# motherboard.net
KiCad netlist of a schematic drawn in Altium Designer
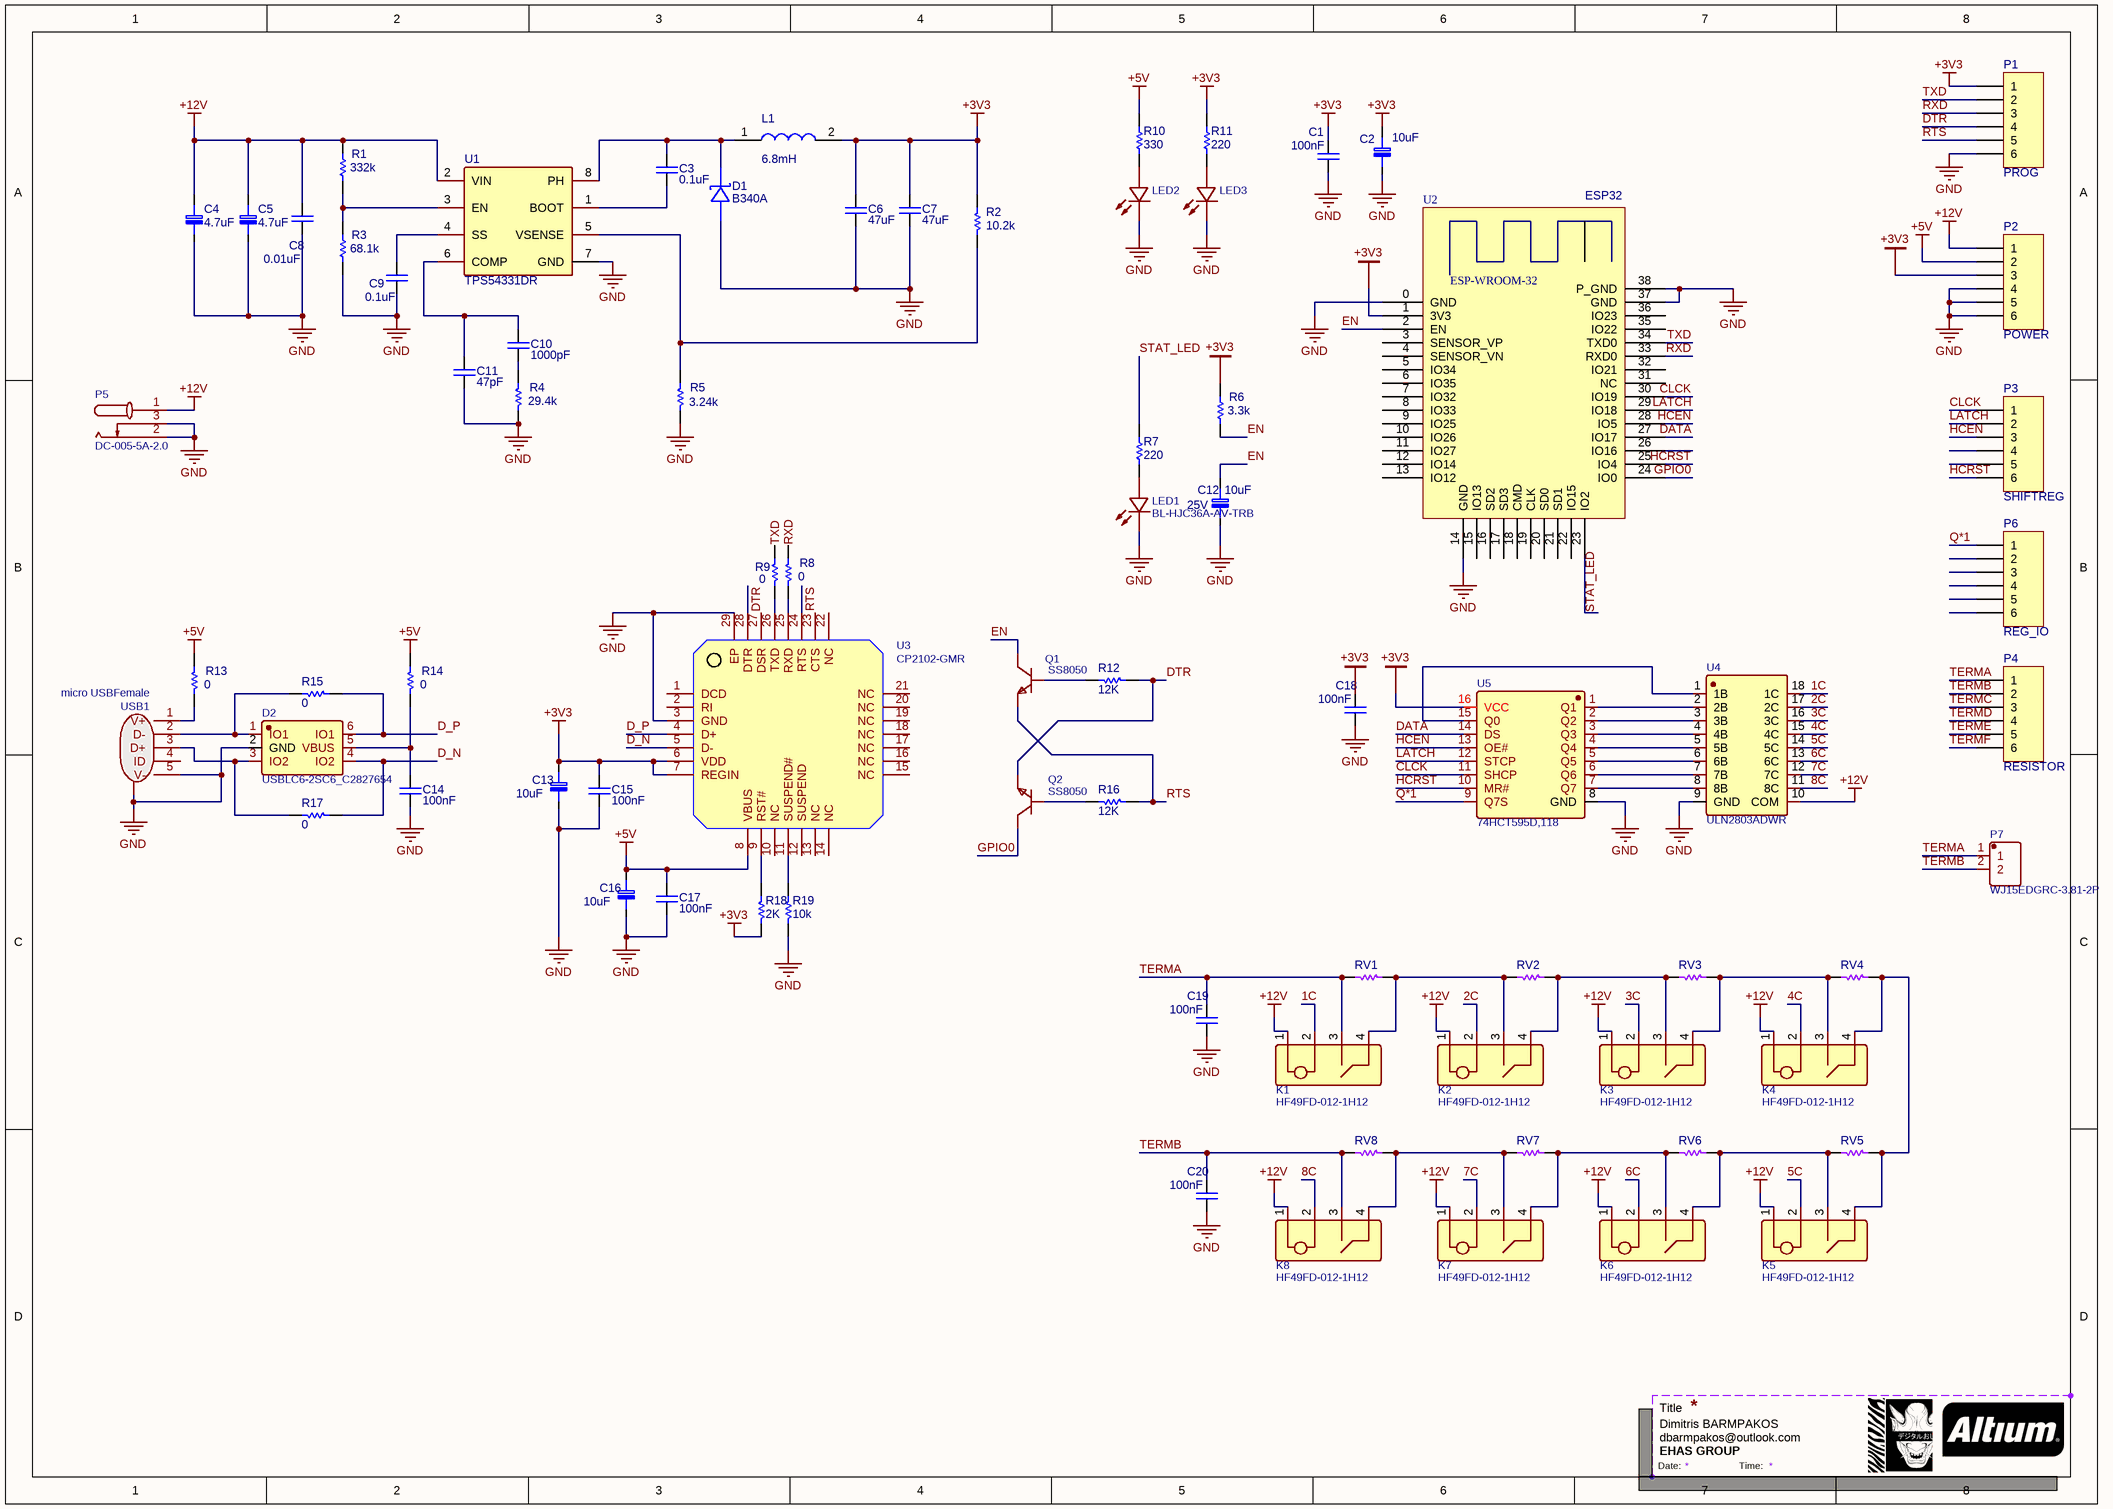
[diagram p0: motherboard.SchDoc]

(export (version "E")
  (design (tool "Eeschema 10.0.6"))
  (components
    (comp (ref "C1")
      (value "100nF")
      (footprint "CAP_0603")
      (description "CAP CER 0.1UF 50V X7R 0603")
      (fields
        (field (name "MANUFACTURER") "FH(Guangdong Fenghua Advanced Tech)")
        (field (name "MANUFACTURER PART NUMBER") "0603F104M500NT")
      )
      (libsource (lib "Schlib1") (part "CAP - CER 0.1UF 25V X7R 0805"))
    )
    (comp (ref "C2")
      (value "22uF 63V")
      (footprint "CAP SMD 6.3X7.7")
      (description "CAP ALUM 22UF 20% 25V SMD")
      (fields
        (field (name "MANUFACTURER") "Nichicon")
        (field (name "MANUFACTURER PART NUMBER") "UWX1E220MCL1GB")
        (field (name "CAPACITANCE") "10uF")
      )
      (libsource (lib "decade_box_lib") (part "CAP POL SMD"))
    )
    (comp (ref "C3")
      (value "0.1uF")
      (footprint "CAP_0603_3D")
      (description "CAP CER 0.1uF 50V C0G/NPO 0603")
      (fields
        (field (name "MANUFACTURER") "Yageo")
        (field (name "MANUFACTURER PART NUMBER") "CC0603JRNPO9BN220")
      )
      (libsource (lib "CC_Main_Lower") (part "Cap 22pF"))
    )
    (comp (ref "C4")
      (value "4.7uF")
      (footprint "CAP-SMD_BD6.3-L6.6-W6.6-LS7.2-R-RD")
      (description "CAP ALUM 22UF 20% 25V SMD")
      (fields
        (field (name "MANUFACTURER") "Nichicon")
        (field (name "MANUFACTURER PART NUMBER") "UWX1E220MCL1GB")
        (field (name "CAPACITANCE") "4.7uF")
      )
      (libsource (lib "decade_box_lib") (part "CAP POL SMD"))
    )
    (comp (ref "C5")
      (value "22uF 63V")
      (footprint "CAP-SMD_BD6.3-L6.6-W6.6-LS7.2-R-RD")
      (description "CAP ALUM 22UF 20% 25V SMD")
      (fields
        (field (name "MANUFACTURER") "Nichicon")
        (field (name "MANUFACTURER PART NUMBER") "UWX1E220MCL1GB")
        (field (name "CAPACITANCE") "4.7uF")
      )
      (libsource (lib "decade_box_lib") (part "CAP POL SMD"))
    )
    (comp (ref "C6")
      (value "47uF")
      (footprint "CAP_0603_3D")
      (description "CAP CER 0.1uF 50V C0G/NPO 0603")
      (fields
        (field (name "MANUFACTURER") "Yageo")
        (field (name "MANUFACTURER PART NUMBER") "CC0603JRNPO9BN220")
      )
      (libsource (lib "CC_Main_Lower") (part "Cap 22pF"))
    )
    (comp (ref "C7")
      (value "47uF")
      (footprint "CAP_0603_3D")
      (description "CAP CER 0.1uF 50V C0G/NPO 0603")
      (fields
        (field (name "MANUFACTURER") "Yageo")
        (field (name "MANUFACTURER PART NUMBER") "CC0603JRNPO9BN220")
      )
      (libsource (lib "CC_Main_Lower") (part "Cap 22pF"))
    )
    (comp (ref "C8")
      (value "0.01uF")
      (footprint "CAP_0603_3D")
      (description "CAP CER 0.1uF 50V C0G/NPO 0603")
      (fields
        (field (name "MANUFACTURER") "Yageo")
        (field (name "MANUFACTURER PART NUMBER") "CC0603JRNPO9BN220")
      )
      (libsource (lib "CC_Main_Lower") (part "Cap 22pF"))
    )
    (comp (ref "C9")
      (value "0.1uF")
      (footprint "CAP_0603_3D")
      (description "CAP CER 0.1uF 50V C0G/NPO 0603")
      (fields
        (field (name "MANUFACTURER") "Yageo")
        (field (name "MANUFACTURER PART NUMBER") "CC0603JRNPO9BN220")
      )
      (libsource (lib "CC_Main_Lower") (part "Cap 22pF"))
    )
    (comp (ref "C10")
      (value "1000pF")
      (footprint "CAP_0603_3D")
      (description "CAP CER 0.1uF 50V C0G/NPO 0603")
      (fields
        (field (name "MANUFACTURER") "Yageo")
        (field (name "MANUFACTURER PART NUMBER") "CC0603JRNPO9BN220")
      )
      (libsource (lib "CC_Main_Lower") (part "Cap 22pF"))
    )
    (comp (ref "C11")
      (value "47pF")
      (footprint "CAP_0603_3D")
      (description "CAP CER 0.1uF 50V C0G/NPO 0603")
      (fields
        (field (name "MANUFACTURER") "Yageo")
        (field (name "MANUFACTURER PART NUMBER") "CC0603JRNPO9BN220")
      )
      (libsource (lib "CC_Main_Lower") (part "Cap 22pF"))
    )
    (comp (ref "C12")
      (value "22uF 63V")
      (footprint "CAP SMD 6.3X7.7")
      (description "CAP ALUM 22UF 20% 25V SMD")
      (fields
        (field (name "MANUFACTURER") "Nichicon")
        (field (name "MANUFACTURER PART NUMBER") "UWX1E220MCL1GB")
        (field (name "CAPACITANCE") "10uF")
        (field (name "VOLTAGE RATING") "25V")
      )
      (libsource (lib "Schlib1") (part "CAP 22UF 63V SMD"))
    )
    (comp (ref "C13")
      (value "4.7uF")
      (footprint "CAP-SMD_BD6.3-L6.6-W6.6-LS7.2-R-RD")
      (description "CAP ALUM 22UF 20% 25V SMD")
      (fields
        (field (name "MANUFACTURER") "Nichicon")
        (field (name "MANUFACTURER PART NUMBER") "UWX1E220MCL1GB")
        (field (name "CAPACITANCE") "10uF")
      )
      (libsource (lib "decade_box_lib") (part "CAP POL SMD"))
    )
    (comp (ref "C14")
      (value "100nF")
      (footprint "CAP_0603_3D")
      (description "CAP CER 0.1uF 50V C0G/NPO 0603")
      (fields
        (field (name "MANUFACTURER") "Yageo")
        (field (name "MANUFACTURER PART NUMBER") "CC0603JRNPO9BN220")
      )
      (libsource (lib "CC_Main_Lower") (part "Cap 22pF"))
    )
    (comp (ref "C15")
      (value "100nF")
      (footprint "CAP_0603_3D")
      (description "CAP CER 0.1uF 50V C0G/NPO 0603")
      (fields
        (field (name "MANUFACTURER") "Yageo")
        (field (name "MANUFACTURER PART NUMBER") "CC0603JRNPO9BN220")
      )
      (libsource (lib "CC_Main_Lower") (part "Cap 22pF"))
    )
    (comp (ref "C16")
      (value "4.7uF")
      (footprint "CAP-SMD_BD6.3-L6.6-W6.6-LS7.2-R-RD")
      (description "CAP ALUM 22UF 20% 25V SMD")
      (fields
        (field (name "MANUFACTURER") "Nichicon")
        (field (name "MANUFACTURER PART NUMBER") "UWX1E220MCL1GB")
        (field (name "CAPACITANCE") "10uF")
      )
      (libsource (lib "decade_box_lib") (part "CAP POL SMD"))
    )
    (comp (ref "C17")
      (value "100nF")
      (footprint "CAP_0603_3D")
      (description "CAP CER 0.1uF 50V C0G/NPO 0603")
      (fields
        (field (name "MANUFACTURER") "Yageo")
        (field (name "MANUFACTURER PART NUMBER") "CC0603JRNPO9BN220")
      )
      (libsource (lib "CC_Main_Lower") (part "Cap 22pF"))
    )
    (comp (ref "C18")
      (value "100nF")
      (footprint "CAP_0603")
      (description "CAP CER 0.1UF 50V X7R 0603")
      (fields
        (field (name "MANUFACTURER") "FH(Guangdong Fenghua Advanced Tech)")
        (field (name "MANUFACTURER PART NUMBER") "0603F104M500NT")
      )
      (libsource (lib "Schlib1") (part "CAP - CER 0.1UF 25V X7R 0805"))
    )
    (comp (ref "C19")
      (value "100nF")
      (footprint "CAP_0603")
      (description "CAP CER 0.1UF 50V X7R 0603")
      (fields
        (field (name "MANUFACTURER") "FH(Guangdong Fenghua Advanced Tech)")
        (field (name "MANUFACTURER PART NUMBER") "0603F104M500NT")
      )
      (libsource (lib "Schlib1") (part "CAP - CER 0.1UF 25V X7R 0805"))
    )
    (comp (ref "C20")
      (value "100nF")
      (footprint "CAP_0603")
      (description "CAP CER 0.1UF 50V X7R 0603")
      (fields
        (field (name "MANUFACTURER") "FH(Guangdong Fenghua Advanced Tech)")
        (field (name "MANUFACTURER PART NUMBER") "0603F104M500NT")
      )
      (libsource (lib "Schlib1") (part "CAP - CER 0.1UF 25V X7R 0805"))
    )
    (comp (ref "D1")
      (value "B340A")
      (footprint "SMA_L4.3-W2.6-LS5.2-RD")
      (fields (field (name "BOM_SUPPLIER PART") "C64982"))
      (libsource (lib "decade_box_lib") (part "B340A"))
    )
    (comp (ref "D2")
      (value "USBLC6-2SC6_C2827654")
      (footprint "SOT-23-6_L2.9-W1.6-P0.95-LS2.8-BL")
      (fields
        (field (name "BOM_SUPPLIER PART") "C2827654")
        (field (name "BOM_MANUFACTURER PART") "USBLC6-2SC6")
        (field (name "CONTRIBUTOR") "LCSC")
      )
      (libsource (lib "decade_box_lib") (part "USBLC6-2SC6_C2827654"))
    )
    (comp (ref "K1")
      (value "HF49FD-012-1H12")
      (footprint "RELAY-TH_HF49FD-0XX-1H12")
      (fields (field (name "BOM_SUPPLIER PART") "C117488") (field (name "CONTRIBUTOR") "LCSC"))
      (libsource (lib "decade_box_lib") (part "HF49FD-012-1H12"))
    )
    (comp (ref "K2")
      (value "HF49FD-012-1H12")
      (footprint "RELAY-TH_HF49FD-0XX-1H12")
      (fields (field (name "BOM_SUPPLIER PART") "C117488") (field (name "CONTRIBUTOR") "LCSC"))
      (libsource (lib "decade_box_lib") (part "HF49FD-012-1H12"))
    )
    (comp (ref "K3")
      (value "HF49FD-012-1H12")
      (footprint "RELAY-TH_HF49FD-0XX-1H12")
      (fields (field (name "BOM_SUPPLIER PART") "C117488") (field (name "CONTRIBUTOR") "LCSC"))
      (libsource (lib "decade_box_lib") (part "HF49FD-012-1H12"))
    )
    (comp (ref "K4")
      (value "HF49FD-012-1H12")
      (footprint "RELAY-TH_HF49FD-0XX-1H12")
      (fields (field (name "BOM_SUPPLIER PART") "C117488") (field (name "CONTRIBUTOR") "LCSC"))
      (libsource (lib "decade_box_lib") (part "HF49FD-012-1H12"))
    )
    (comp (ref "K5")
      (value "HF49FD-012-1H12")
      (footprint "RELAY-TH_HF49FD-0XX-1H12")
      (fields (field (name "BOM_SUPPLIER PART") "C117488") (field (name "CONTRIBUTOR") "LCSC"))
      (libsource (lib "decade_box_lib") (part "HF49FD-012-1H12"))
    )
    (comp (ref "K6")
      (value "HF49FD-012-1H12")
      (footprint "RELAY-TH_HF49FD-0XX-1H12")
      (fields (field (name "BOM_SUPPLIER PART") "C117488") (field (name "CONTRIBUTOR") "LCSC"))
      (libsource (lib "decade_box_lib") (part "HF49FD-012-1H12"))
    )
    (comp (ref "K7")
      (value "HF49FD-012-1H12")
      (footprint "RELAY-TH_HF49FD-0XX-1H12")
      (fields (field (name "BOM_SUPPLIER PART") "C117488") (field (name "CONTRIBUTOR") "LCSC"))
      (libsource (lib "decade_box_lib") (part "HF49FD-012-1H12"))
    )
    (comp (ref "K8")
      (value "HF49FD-012-1H12")
      (footprint "RELAY-TH_HF49FD-0XX-1H12")
      (fields (field (name "BOM_SUPPLIER PART") "C117488") (field (name "CONTRIBUTOR") "LCSC"))
      (libsource (lib "decade_box_lib") (part "HF49FD-012-1H12"))
    )
    (comp (ref "L1")
      (value "6.8mH")
      (footprint "L_4018")
      (description "C393989")
      (libsource (lib "Schlib1") (part "L"))
    )
    (comp (ref "LED1")
      (value "BL-HJC36A-AV-TRB")
      (footprint "LED0603-RD_ORANGE")
      (fields (field (name "BOM_SUPPLIER PART") "C138546") (field (name "CONTRIBUTOR") "LCSC"))
      (libsource (lib "decade_box_lib") (part "BL-HJC36A-AV-TRB"))
    )
    (comp (ref "LED2")
      (value "BL-HJC36A-AV-TRB")
      (footprint "LED0603-RD_ORANGE")
      (fields (field (name "BOM_SUPPLIER PART") "C138546") (field (name "CONTRIBUTOR") "LCSC"))
      (libsource (lib "decade_box_lib") (part "BL-HJC36A-AV-TRB"))
    )
    (comp (ref "LED3")
      (value "BL-HJC36A-AV-TRB")
      (footprint "LED0603-RD_ORANGE")
      (fields (field (name "BOM_SUPPLIER PART") "C138546") (field (name "CONTRIBUTOR") "LCSC"))
      (libsource (lib "decade_box_lib") (part "BL-HJC36A-AV-TRB"))
    )
    (comp (ref "P1")
      (value "PROG")
      (footprint "HDR1X6")
      (description "Header, 6-Pin")
      (fields (field (name "PUBLISHER") "Altium Limited"))
      (libsource (lib "decade_box_lib") (part "Header 6"))
    )
    (comp (ref "P2")
      (value "POWER")
      (footprint "HDR1X6")
      (description "Header, 6-Pin")
      (fields (field (name "PUBLISHER") "Altium Limited"))
      (libsource (lib "decade_box_lib") (part "Header 6"))
    )
    (comp (ref "P3")
      (value "SHIFTREG")
      (footprint "HDR1X6")
      (description "Header, 6-Pin")
      (fields (field (name "PUBLISHER") "Altium Limited"))
      (libsource (lib "decade_box_lib") (part "Header 6"))
    )
    (comp (ref "P4")
      (value "RESISTOR")
      (footprint "HDR1X6")
      (description "Header, 6-Pin")
      (fields (field (name "PUBLISHER") "Altium Limited"))
      (libsource (lib "decade_box_lib") (part "Header 6"))
    )
    (comp (ref "P5")
      (value "DC-005-5A-2.0")
      (footprint "DC-IN-TH_DC-005-5A-2.0")
      (fields (field (name "BOM_SUPPLIER PART") "C381116") (field (name "CONTRIBUTOR") "LCSC"))
      (libsource (lib "decade_box_lib") (part "DC-005-5A-2.0"))
    )
    (comp (ref "P6")
      (value "REG_IO")
      (footprint "HDR1X6")
      (description "Header, 6-Pin")
      (fields (field (name "PUBLISHER") "Altium Limited"))
      (libsource (lib "decade_box_lib") (part "Header 6"))
    )
    (comp (ref "P7")
      (value "WJ15EDGRC-3.81-2P")
      (footprint "CONN-TH_2P-P3.81_WJ15EDGRC-3.81-2P")
      (description "C8387")
      (libsource (lib "Schlib1") (part "WJ15EDGRC-3.81-2P"))
    )
    (comp (ref "Q1")
      (value "SS8050")
      (footprint "SOT-23-3_L2.9-W1.3-P1.90-LS2.4-BR")
      (fields (field (name "BOM_SUPPLIER PART") "C2150"))
      (libsource (lib "decade_box_lib") (part "SS8050_C2150"))
    )
    (comp (ref "Q2")
      (value "SS8050")
      (footprint "SOT-23-3_L2.9-W1.3-P1.90-LS2.4-BR")
      (fields (field (name "BOM_SUPPLIER PART") "C2150"))
      (libsource (lib "decade_box_lib") (part "SS8050_C2150"))
    )
    (comp (ref "R1")
      (value "Res1")
      (footprint "R0603")
      (description "Res Thick Film 0603 1M Ohm 1% 0.1W(1/10W) ±100ppm/C Pad SMD T/R")
      (fields
        (field (name "MANUFACTURER") "TE Connectivity")
        (field (name "MANUFACTURER PART NUMBER") "CRG0603F1M0")
        (field (name "RESISTANCE") "332k")
      )
      (libsource (lib "Miscellaneous Devices") (part "Res1"))
    )
    (comp (ref "R2")
      (value "Res1")
      (footprint "R0603")
      (description "Res Thick Film 0603 1M Ohm 1% 0.1W(1/10W) ±100ppm/C Pad SMD T/R")
      (fields
        (field (name "MANUFACTURER") "TE Connectivity")
        (field (name "MANUFACTURER PART NUMBER") "CRG0603F1M0")
        (field (name "RESISTANCE") "10.2k")
      )
      (libsource (lib "Miscellaneous Devices") (part "Res1"))
    )
    (comp (ref "R3")
      (value "Res1")
      (footprint "R0603")
      (description "Res Thick Film 0603 1M Ohm 1% 0.1W(1/10W) ±100ppm/C Pad SMD T/R")
      (fields
        (field (name "MANUFACTURER") "TE Connectivity")
        (field (name "MANUFACTURER PART NUMBER") "CRG0603F1M0")
        (field (name "RESISTANCE") "68.1k")
      )
      (libsource (lib "Miscellaneous Devices") (part "Res1"))
    )
    (comp (ref "R4")
      (value "Res1")
      (footprint "R0603")
      (description "Res Thick Film 0603 1M Ohm 1% 0.1W(1/10W) ±100ppm/C Pad SMD T/R")
      (fields
        (field (name "MANUFACTURER") "TE Connectivity")
        (field (name "MANUFACTURER PART NUMBER") "CRG0603F1M0")
        (field (name "RESISTANCE") "29.4k")
      )
      (libsource (lib "Miscellaneous Devices") (part "Res1"))
    )
    (comp (ref "R5")
      (value "Res1")
      (footprint "R0603")
      (description "Res Thick Film 0603 1M Ohm 1% 0.1W(1/10W) ±100ppm/C Pad SMD T/R")
      (fields
        (field (name "MANUFACTURER") "TE Connectivity")
        (field (name "MANUFACTURER PART NUMBER") "CRG0603F1M0")
        (field (name "RESISTANCE") "3.24k")
      )
      (libsource (lib "Miscellaneous Devices") (part "Res1"))
    )
    (comp (ref "R6")
      (value "Res1")
      (footprint "R0603")
      (description "Res Thick Film 0603 1M Ohm 1% 0.1W(1/10W) ±100ppm/C Pad SMD T/R")
      (fields
        (field (name "MANUFACTURER") "TE Connectivity")
        (field (name "MANUFACTURER PART NUMBER") "CRG0603F1M0")
        (field (name "RESISTANCE") "3.3k")
      )
      (libsource (lib "Miscellaneous Devices") (part "Res1"))
    )
    (comp (ref "R7")
      (value "Res1")
      (footprint "R0603")
      (description "Res Thick Film 0603 1M Ohm 1% 0.1W(1/10W) ±100ppm/C Pad SMD T/R")
      (fields
        (field (name "MANUFACTURER") "TE Connectivity")
        (field (name "MANUFACTURER PART NUMBER") "CRG0603F1M0")
        (field (name "RESISTANCE") "220")
      )
      (libsource (lib "Miscellaneous Devices") (part "Res1"))
    )
    (comp (ref "R8")
      (value "Res1")
      (footprint "R0603")
      (description "Res Thick Film 0603 1M Ohm 1% 0.1W(1/10W) ±100ppm/C Pad SMD T/R")
      (fields
        (field (name "MANUFACTURER") "TE Connectivity")
        (field (name "MANUFACTURER PART NUMBER") "CRG0603F1M0")
        (field (name "RESISTANCE") "0")
      )
      (libsource (lib "Miscellaneous Devices") (part "Res1"))
    )
    (comp (ref "R9")
      (value "Res1")
      (footprint "R0603")
      (description "Res Thick Film 0603 1M Ohm 1% 0.1W(1/10W) ±100ppm/C Pad SMD T/R")
      (fields
        (field (name "MANUFACTURER") "TE Connectivity")
        (field (name "MANUFACTURER PART NUMBER") "CRG0603F1M0")
        (field (name "RESISTANCE") "0")
      )
      (libsource (lib "Miscellaneous Devices") (part "Res1"))
    )
    (comp (ref "R10")
      (value "Res1")
      (footprint "R0603")
      (description "Res Thick Film 0603 1M Ohm 1% 0.1W(1/10W) ±100ppm/C Pad SMD T/R")
      (fields
        (field (name "MANUFACTURER") "TE Connectivity")
        (field (name "MANUFACTURER PART NUMBER") "CRG0603F1M0")
        (field (name "RESISTANCE") "330")
      )
      (libsource (lib "Miscellaneous Devices") (part "Res1"))
    )
    (comp (ref "R11")
      (value "Res1")
      (footprint "R0603")
      (description "Res Thick Film 0603 1M Ohm 1% 0.1W(1/10W) ±100ppm/C Pad SMD T/R")
      (fields
        (field (name "MANUFACTURER") "TE Connectivity")
        (field (name "MANUFACTURER PART NUMBER") "CRG0603F1M0")
        (field (name "RESISTANCE") "220")
      )
      (libsource (lib "Miscellaneous Devices") (part "Res1"))
    )
    (comp (ref "R12")
      (value "Res1")
      (footprint "R0603")
      (description "Res Thkflm Anti-sulfurated 0603 100K Ohm 5% SMD")
      (fields
        (field (name "MANUFACTURER") "Panasonic")
        (field (name "MANUFACTURER PART NUMBER") "ERJ-U03J104V")
        (field (name "RESISTANCE") "12K")
      )
      (libsource (lib "Altium_Library") (part "Res1"))
    )
    (comp (ref "R13")
      (value "Res1")
      (footprint "R0603")
      (description "Res Thick Film 0603 1M Ohm 1% 0.1W(1/10W) ±100ppm/C Pad SMD T/R")
      (fields
        (field (name "MANUFACTURER") "TE Connectivity")
        (field (name "MANUFACTURER PART NUMBER") "CRG0603F1M0")
        (field (name "RESISTANCE") "0")
      )
      (libsource (lib "Miscellaneous Devices") (part "Res1"))
    )
    (comp (ref "R14")
      (value "Res1")
      (footprint "R0603")
      (description "Res Thick Film 0603 1M Ohm 1% 0.1W(1/10W) ±100ppm/C Pad SMD T/R")
      (fields
        (field (name "MANUFACTURER") "TE Connectivity")
        (field (name "MANUFACTURER PART NUMBER") "CRG0603F1M0")
        (field (name "RESISTANCE") "0")
      )
      (libsource (lib "Miscellaneous Devices") (part "Res1"))
    )
    (comp (ref "R15")
      (value "Res1")
      (footprint "R0603")
      (description "Res Thick Film 0603 1M Ohm 1% 0.1W(1/10W) ±100ppm/C Pad SMD T/R")
      (fields
        (field (name "MANUFACTURER") "TE Connectivity")
        (field (name "MANUFACTURER PART NUMBER") "CRG0603F1M0")
        (field (name "RESISTANCE") "0")
      )
      (libsource (lib "Miscellaneous Devices") (part "Res1"))
    )
    (comp (ref "R16")
      (value "Res1")
      (footprint "R0603")
      (description "Res Thkflm Anti-sulfurated 0603 100K Ohm 5% SMD")
      (fields
        (field (name "MANUFACTURER") "Panasonic")
        (field (name "MANUFACTURER PART NUMBER") "ERJ-U03J104V")
        (field (name "RESISTANCE") "12K")
      )
      (libsource (lib "Altium_Library") (part "Res1"))
    )
    (comp (ref "R17")
      (value "Res1")
      (footprint "R0603")
      (description "Res Thick Film 0603 1M Ohm 1% 0.1W(1/10W) ±100ppm/C Pad SMD T/R")
      (fields
        (field (name "MANUFACTURER") "TE Connectivity")
        (field (name "MANUFACTURER PART NUMBER") "CRG0603F1M0")
        (field (name "RESISTANCE") "0")
      )
      (libsource (lib "Miscellaneous Devices") (part "Res1"))
    )
    (comp (ref "R18")
      (value "Res1")
      (footprint "R0603")
      (description "Res Thick Film 0603 1M Ohm 1% 0.1W(1/10W) ±100ppm/C Pad SMD T/R")
      (fields
        (field (name "MANUFACTURER") "TE Connectivity")
        (field (name "MANUFACTURER PART NUMBER") "CRG0603F1M0")
        (field (name "RESISTANCE") "2K")
      )
      (libsource (lib "Miscellaneous Devices") (part "Res1"))
    )
    (comp (ref "R19")
      (value "Res1")
      (footprint "R0603")
      (description "Res Thick Film 0603 1M Ohm 1% 0.1W(1/10W) ±100ppm/C Pad SMD T/R")
      (fields
        (field (name "MANUFACTURER") "TE Connectivity")
        (field (name "MANUFACTURER PART NUMBER") "CRG0603F1M0")
        (field (name "RESISTANCE") "10k")
      )
      (libsource (lib "Miscellaneous Devices") (part "Res1"))
    )
    (comp (ref "RV1")
      (value "RV")
      (footprint "RES_PLACEHOLDER")
      (description "Placeholder for resistor")
      (fields
        (field (name "MANUFACTURER") "Panasonic")
        (field (name "MANUFACTURER PART NUMBER") "ERJ-U03J104V")
      )
      (libsource (lib "decade_box_lib") (part "RV"))
    )
    (comp (ref "RV2")
      (value "RV")
      (footprint "RES_PLACEHOLDER")
      (description "Placeholder for resistor")
      (fields
        (field (name "MANUFACTURER") "Panasonic")
        (field (name "MANUFACTURER PART NUMBER") "ERJ-U03J104V")
      )
      (libsource (lib "decade_box_lib") (part "RV"))
    )
    (comp (ref "RV3")
      (value "RV")
      (footprint "RES_PLACEHOLDER")
      (description "Placeholder for resistor")
      (fields
        (field (name "MANUFACTURER") "Panasonic")
        (field (name "MANUFACTURER PART NUMBER") "ERJ-U03J104V")
      )
      (libsource (lib "decade_box_lib") (part "RV"))
    )
    (comp (ref "RV4")
      (value "RV")
      (footprint "RES_PLACEHOLDER")
      (description "Placeholder for resistor")
      (fields
        (field (name "MANUFACTURER") "Panasonic")
        (field (name "MANUFACTURER PART NUMBER") "ERJ-U03J104V")
      )
      (libsource (lib "decade_box_lib") (part "RV"))
    )
    (comp (ref "RV5")
      (value "RV")
      (footprint "RES_PLACEHOLDER")
      (description "Placeholder for resistor")
      (fields
        (field (name "MANUFACTURER") "Panasonic")
        (field (name "MANUFACTURER PART NUMBER") "ERJ-U03J104V")
      )
      (libsource (lib "decade_box_lib") (part "RV"))
    )
    (comp (ref "RV6")
      (value "RV")
      (footprint "RES_PLACEHOLDER")
      (description "Placeholder for resistor")
      (fields
        (field (name "MANUFACTURER") "Panasonic")
        (field (name "MANUFACTURER PART NUMBER") "ERJ-U03J104V")
      )
      (libsource (lib "decade_box_lib") (part "RV"))
    )
    (comp (ref "RV7")
      (value "RV")
      (footprint "RES_PLACEHOLDER")
      (description "Placeholder for resistor")
      (fields
        (field (name "MANUFACTURER") "Panasonic")
        (field (name "MANUFACTURER PART NUMBER") "ERJ-U03J104V")
      )
      (libsource (lib "decade_box_lib") (part "RV"))
    )
    (comp (ref "RV8")
      (value "RV")
      (footprint "RES_PLACEHOLDER")
      (description "Placeholder for resistor")
      (fields
        (field (name "MANUFACTURER") "Panasonic")
        (field (name "MANUFACTURER PART NUMBER") "ERJ-U03J104V")
      )
      (libsource (lib "decade_box_lib") (part "RV"))
    )
    (comp (ref "U1")
      (value "TPS54331DR")
      (footprint "SOIC-8_L5.0-W4.0-P1.27-LS6.0-BL")
      (fields (field (name "BOM_SUPPLIER PART") "C9865"))
      (libsource (lib "decade_box_lib") (part "TPS54331DR"))
    )
    (comp (ref "U2")
      (value "ESP32")
      (footprint "ESP32_WROOM")
      (description "ESP 32")
      (libsource (lib "Schlib1") (part "ESP 32"))
    )
    (comp (ref "U3")
      (value "CP2102-GMR")
      (footprint "WQFN-28_L5.0-W5.0-P0.50-BL-EP3.2")
      (fields (field (name "BOM_SUPPLIER PART") "C6568"))
      (libsource (lib "decade_box_lib") (part "CP2102-GMR"))
    )
    (comp (ref "U4")
      (value "ULN2803ADWR")
      (footprint "SOIC-18_L11.6-W7.5-P1.27-LS10.3-BL")
      (fields (field (name "BOM_SUPPLIER PART") "C9683"))
      (libsource (lib "decade_box_lib") (part "ULN2803ADWR"))
    )
    (comp (ref "U5")
      (value "74HCT595D,118")
      (footprint "SOIC-16_L9.9-W3.9-P1.27-LS6.0-BL")
      (fields (field (name "BOM_SUPPLIER PART") "C282339") (field (name "CONTRIBUTOR") "LCSC"))
      (libsource (lib "decade_box_lib") (part "74HCT595D,118"))
    )
    (comp (ref "USB1")
      (value "micro USBFemale")
      (footprint "MICRO-USB-SMD_5P-P0.65-H-F_C10418")
      (fields (field (name "BOM_SUPPLIER PART") "C10418"))
      (libsource (lib "decade_box_lib") (part "micro USBFemale"))
    )
  )
  (nets
    (net (code "1") (name "+3V3") (class "Default")
      (node (ref "C1") (pin "1") (pinfunction "1_1") (pintype "passive"))
      (node (ref "C13") (pin "1") (pinfunction "1_1") (pintype "passive"))
      (node (ref "C15") (pin "1") (pinfunction "1_1") (pintype "passive"))
      (node (ref "C18") (pin "1") (pinfunction "1_1") (pintype "passive"))
      (node (ref "C2") (pin "1") (pinfunction "1_1") (pintype "passive"))
      (node (ref "C6") (pin "1") (pinfunction "1_1") (pintype "passive"))
      (node (ref "C7") (pin "1") (pinfunction "1_1") (pintype "passive"))
      (node (ref "L1") (pin "2") (pinfunction "2_2") (pintype "passive"))
      (node (ref "P1") (pin "1") (pinfunction "1_1") (pintype "passive"))
      (node (ref "P2") (pin "3") (pinfunction "3_3") (pintype "passive"))
      (node (ref "R11") (pin "2") (pinfunction "2_2") (pintype "passive"))
      (node (ref "R18") (pin "1") (pinfunction "1_1") (pintype "passive"))
      (node (ref "R2") (pin "1") (pinfunction "1_1") (pintype "passive"))
      (node (ref "R6") (pin "1") (pinfunction "1_1") (pintype "passive"))
      (node (ref "U2") (pin "1") (pinfunction "3V3_1") (pintype "passive"))
      (node (ref "U3") (pin "6") (pinfunction "VDD_6") (pintype "passive"))
      (node (ref "U3") (pin "7") (pinfunction "REGIN_7") (pintype "passive"))
      (node (ref "U5") (pin "16") (pinfunction "VCC_16") (pintype "passive"))
    )
    (net (code "2") (name "+5V") (class "Default")
      (node (ref "C16") (pin "1") (pinfunction "1_1") (pintype "passive"))
      (node (ref "C17") (pin "1") (pinfunction "1_1") (pintype "passive"))
      (node (ref "P2") (pin "2") (pinfunction "2_2") (pintype "passive"))
      (node (ref "R10") (pin "2") (pinfunction "2_2") (pintype "passive"))
      (node (ref "R13") (pin "1") (pinfunction "1_1") (pintype "passive"))
      (node (ref "R14") (pin "1") (pinfunction "1_1") (pintype "passive"))
      (node (ref "U3") (pin "8") (pinfunction "VBUS_8") (pintype "passive"))
    )
    (net (code "3") (name "+12V") (class "Default")
      (node (ref "C4") (pin "1") (pinfunction "1_1") (pintype "passive"))
      (node (ref "C5") (pin "1") (pinfunction "1_1") (pintype "passive"))
      (node (ref "C8") (pin "1") (pinfunction "1_1") (pintype "passive"))
      (node (ref "K1") (pin "1") (pinfunction "1_1") (pintype "passive"))
      (node (ref "K2") (pin "1") (pinfunction "1_1") (pintype "passive"))
      (node (ref "K3") (pin "1") (pinfunction "1_1") (pintype "passive"))
      (node (ref "K4") (pin "1") (pinfunction "1_1") (pintype "passive"))
      (node (ref "K5") (pin "1") (pinfunction "1_1") (pintype "passive"))
      (node (ref "K6") (pin "1") (pinfunction "1_1") (pintype "passive"))
      (node (ref "K7") (pin "1") (pinfunction "1_1") (pintype "passive"))
      (node (ref "K8") (pin "1") (pinfunction "1_1") (pintype "passive"))
      (node (ref "P2") (pin "1") (pinfunction "1_1") (pintype "passive"))
      (node (ref "P5") (pin "1") (pinfunction "1_1") (pintype "passive"))
      (node (ref "R1") (pin "1") (pinfunction "1_1") (pintype "passive"))
      (node (ref "U1") (pin "2") (pinfunction "VIN_2") (pintype "passive"))
      (node (ref "U4") (pin "10") (pinfunction "COM_10") (pintype "passive"))
    )
    (net (code "4") (name "/1C") (class "Default")
      (node (ref "K1") (pin "2") (pinfunction "2_2") (pintype "passive"))
      (node (ref "U4") (pin "18") (pinfunction "1C_18") (pintype "passive"))
    )
    (net (code "5") (name "/2C") (class "Default")
      (node (ref "K2") (pin "2") (pinfunction "2_2") (pintype "passive"))
      (node (ref "U4") (pin "17") (pinfunction "2C_17") (pintype "passive"))
    )
    (net (code "6") (name "/3C") (class "Default")
      (node (ref "K3") (pin "2") (pinfunction "2_2") (pintype "passive"))
      (node (ref "U4") (pin "16") (pinfunction "3C_16") (pintype "passive"))
    )
    (net (code "7") (name "/4C") (class "Default")
      (node (ref "K4") (pin "2") (pinfunction "2_2") (pintype "passive"))
      (node (ref "U4") (pin "15") (pinfunction "4C_15") (pintype "passive"))
    )
    (net (code "8") (name "/5C") (class "Default")
      (node (ref "K5") (pin "2") (pinfunction "2_2") (pintype "passive"))
      (node (ref "U4") (pin "14") (pinfunction "5C_14") (pintype "passive"))
    )
    (net (code "9") (name "/6C") (class "Default")
      (node (ref "K6") (pin "2") (pinfunction "2_2") (pintype "passive"))
      (node (ref "U4") (pin "13") (pinfunction "6C_13") (pintype "passive"))
    )
    (net (code "10") (name "/7C") (class "Default")
      (node (ref "K7") (pin "2") (pinfunction "2_2") (pintype "passive"))
      (node (ref "U4") (pin "12") (pinfunction "7C_12") (pintype "passive"))
    )
    (net (code "11") (name "/8C") (class "Default")
      (node (ref "K8") (pin "2") (pinfunction "2_2") (pintype "passive"))
      (node (ref "U4") (pin "11") (pinfunction "8C_11") (pintype "passive"))
    )
    (net (code "12") (name "/CLCK") (class "Default")
      (node (ref "P3") (pin "1") (pinfunction "1_1") (pintype "passive"))
      (node (ref "U2") (pin "30") (pinfunction "IO19_30") (pintype "passive"))
      (node (ref "U5") (pin "11") (pinfunction "SHCP_11") (pintype "passive"))
    )
    (net (code "13") (name "/DATA") (class "Default")
      (node (ref "U2") (pin "27") (pinfunction "IO17_27") (pintype "passive"))
      (node (ref "U5") (pin "14") (pinfunction "DS_14") (pintype "passive"))
    )
    (net (code "14") (name "/DTR") (class "Default")
      (node (ref "P1") (pin "4") (pinfunction "4_4") (pintype "passive"))
      (node (ref "Q2") (pin "2") (pinfunction "E_2") (pintype "passive"))
      (node (ref "R12") (pin "2") (pinfunction "2_2") (pintype "passive"))
      (node (ref "U3") (pin "28") (pinfunction "DTR_28") (pintype "passive"))
    )
    (net (code "15") (name "/D_N") (class "Default")
      (node (ref "D2") (pin "4") (pinfunction "IO2_4") (pintype "passive"))
      (node (ref "R17") (pin "2") (pinfunction "2_2") (pintype "passive"))
      (node (ref "U3") (pin "5") (pinfunction "D-_5") (pintype "passive"))
    )
    (net (code "16") (name "/D_P") (class "Default")
      (node (ref "D2") (pin "6") (pinfunction "IO1_6") (pintype "passive"))
      (node (ref "R15") (pin "2") (pinfunction "2_2") (pintype "passive"))
      (node (ref "U3") (pin "4") (pinfunction "D+_4") (pintype "passive"))
    )
    (net (code "17") (name "/EN") (class "Default")
      (node (ref "C12") (pin "1") (pinfunction "1_1") (pintype "passive"))
      (node (ref "Q1") (pin "3") (pinfunction "C_3") (pintype "passive"))
      (node (ref "R6") (pin "2") (pinfunction "2_2") (pintype "passive"))
      (node (ref "U2") (pin "2") (pinfunction "EN_2") (pintype "passive"))
    )
    (net (code "18") (name "/GPIO0") (class "Default")
      (node (ref "Q2") (pin "3") (pinfunction "C_3") (pintype "passive"))
      (node (ref "U2") (pin "24") (pinfunction "IO0_24") (pintype "passive"))
    )
    (net (code "19") (name "/HCEN") (class "Default")
      (node (ref "P3") (pin "3") (pinfunction "3_3") (pintype "passive"))
      (node (ref "U2") (pin "28") (pinfunction "IO5_28") (pintype "passive"))
      (node (ref "U5") (pin "13") (pinfunction "OE#_13") (pintype "passive"))
    )
    (net (code "20") (name "/HCRST") (class "Default")
      (node (ref "P3") (pin "6") (pinfunction "6_6") (pintype "passive"))
      (node (ref "U2") (pin "25") (pinfunction "IO4_25") (pintype "passive"))
      (node (ref "U5") (pin "10") (pinfunction "MR#_10") (pintype "passive"))
    )
    (net (code "21") (name "/LATCH") (class "Default")
      (node (ref "P3") (pin "2") (pinfunction "2_2") (pintype "passive"))
      (node (ref "U2") (pin "29") (pinfunction "IO18_29") (pintype "passive"))
      (node (ref "U5") (pin "12") (pinfunction "STCP_12") (pintype "passive"))
    )
    (net (code "22") (name "/Q*1") (class "Default")
      (node (ref "P6") (pin "1") (pinfunction "1_1") (pintype "passive"))
      (node (ref "U5") (pin "9") (pinfunction "Q7S_9") (pintype "passive"))
    )
    (net (code "23") (name "/RTS") (class "Default")
      (node (ref "P1") (pin "5") (pinfunction "5_5") (pintype "passive"))
      (node (ref "Q1") (pin "2") (pinfunction "E_2") (pintype "passive"))
      (node (ref "R16") (pin "2") (pinfunction "2_2") (pintype "passive"))
      (node (ref "U3") (pin "24") (pinfunction "RTS_24") (pintype "passive"))
    )
    (net (code "24") (name "/RXD") (class "Default")
      (node (ref "P1") (pin "3") (pinfunction "3_3") (pintype "passive"))
      (node (ref "R8") (pin "1") (pinfunction "1_1") (pintype "passive"))
      (node (ref "U2") (pin "33") (pinfunction "RXD0_33") (pintype "passive"))
    )
    (net (code "25") (name "/STAT_LED") (class "Default")
      (node (ref "R7") (pin "2") (pinfunction "2_2") (pintype "passive"))
      (node (ref "U2") (pin "23") (pinfunction "IO2_23") (pintype "passive"))
    )
    (net (code "26") (name "/TERMA") (class "Default")
      (node (ref "C19") (pin "1") (pinfunction "1_1") (pintype "passive"))
      (node (ref "K1") (pin "3") (pinfunction "3_3") (pintype "passive"))
      (node (ref "P4") (pin "1") (pinfunction "1_1") (pintype "passive"))
      (node (ref "P7") (pin "1") (pinfunction "1_1") (pintype "passive"))
      (node (ref "RV1") (pin "2") (pinfunction "2_2") (pintype "passive"))
    )
    (net (code "27") (name "/TERMB") (class "Default")
      (node (ref "C20") (pin "1") (pinfunction "1_1") (pintype "passive"))
      (node (ref "K8") (pin "3") (pinfunction "3_3") (pintype "passive"))
      (node (ref "P4") (pin "2") (pinfunction "2_2") (pintype "passive"))
      (node (ref "P7") (pin "2") (pinfunction "2_2") (pintype "passive"))
      (node (ref "RV8") (pin "2") (pinfunction "2_2") (pintype "passive"))
    )
    (net (code "28") (name "/TERMC") (class "Default")
      (node (ref "P4") (pin "3") (pinfunction "3_3") (pintype "passive"))
    )
    (net (code "29") (name "/TERMD") (class "Default")
      (node (ref "P4") (pin "4") (pinfunction "4_4") (pintype "passive"))
    )
    (net (code "30") (name "/TERME") (class "Default")
      (node (ref "P4") (pin "5") (pinfunction "5_5") (pintype "passive"))
    )
    (net (code "31") (name "/TERMF") (class "Default")
      (node (ref "P4") (pin "6") (pinfunction "6_6") (pintype "passive"))
    )
    (net (code "32") (name "/TXD") (class "Default")
      (node (ref "P1") (pin "2") (pinfunction "2_2") (pintype "passive"))
      (node (ref "R9") (pin "1") (pinfunction "1_1") (pintype "passive"))
      (node (ref "U2") (pin "34") (pinfunction "TXD0_34") (pintype "passive"))
    )
    (net (code "33") (name "GND") (class "Default")
      (node (ref "C1") (pin "2") (pinfunction "2_2") (pintype "passive"))
      (node (ref "C11") (pin "2") (pinfunction "2_2") (pintype "passive"))
      (node (ref "C12") (pin "2") (pinfunction "2_2") (pintype "passive"))
      (node (ref "C13") (pin "2") (pinfunction "2_2") (pintype "passive"))
      (node (ref "C14") (pin "2") (pinfunction "2_2") (pintype "passive"))
      (node (ref "C15") (pin "2") (pinfunction "2_2") (pintype "passive"))
      (node (ref "C16") (pin "2") (pinfunction "2_2") (pintype "passive"))
      (node (ref "C17") (pin "2") (pinfunction "2_2") (pintype "passive"))
      (node (ref "C18") (pin "2") (pinfunction "2_2") (pintype "passive"))
      (node (ref "C19") (pin "2") (pinfunction "2_2") (pintype "passive"))
      (node (ref "C2") (pin "2") (pinfunction "2_2") (pintype "passive"))
      (node (ref "C20") (pin "2") (pinfunction "2_2") (pintype "passive"))
      (node (ref "C4") (pin "2") (pinfunction "2_2") (pintype "passive"))
      (node (ref "C5") (pin "2") (pinfunction "2_2") (pintype "passive"))
      (node (ref "C6") (pin "2") (pinfunction "2_2") (pintype "passive"))
      (node (ref "C7") (pin "2") (pinfunction "2_2") (pintype "passive"))
      (node (ref "C8") (pin "2") (pinfunction "2_2") (pintype "passive"))
      (node (ref "C9") (pin "2") (pinfunction "2_2") (pintype "passive"))
      (node (ref "D1") (pin "2") (pinfunction "A_2") (pintype "passive"))
      (node (ref "D2") (pin "2") (pinfunction "GND_2") (pintype "passive"))
      (node (ref "LED1") (pin "1") (pinfunction "K_1") (pintype "passive"))
      (node (ref "LED2") (pin "1") (pinfunction "K_1") (pintype "passive"))
      (node (ref "LED3") (pin "1") (pinfunction "K_1") (pintype "passive"))
      (node (ref "P1") (pin "6") (pinfunction "6_6") (pintype "passive"))
      (node (ref "P2") (pin "4") (pinfunction "4_4") (pintype "passive"))
      (node (ref "P2") (pin "5") (pinfunction "5_5") (pintype "passive"))
      (node (ref "P2") (pin "6") (pinfunction "6_6") (pintype "passive"))
      (node (ref "P5") (pin "2") (pinfunction "2_2") (pintype "passive"))
      (node (ref "P5") (pin "3") (pinfunction "3_3") (pintype "passive"))
      (node (ref "R19") (pin "1") (pinfunction "1_1") (pintype "passive"))
      (node (ref "R3") (pin "2") (pinfunction "2_2") (pintype "passive"))
      (node (ref "R4") (pin "2") (pinfunction "2_2") (pintype "passive"))
      (node (ref "R5") (pin "2") (pinfunction "2_2") (pintype "passive"))
      (node (ref "U1") (pin "7") (pinfunction "GND_7") (pintype "passive"))
      (node (ref "U2") (pin "0") (pinfunction "GND_0") (pintype "passive"))
      (node (ref "U2") (pin "14") (pinfunction "GND_14") (pintype "passive"))
      (node (ref "U2") (pin "37") (pinfunction "GND_37") (pintype "passive"))
      (node (ref "U2") (pin "38") (pinfunction "P_GND_38") (pintype "passive"))
      (node (ref "U3") (pin "29") (pinfunction "EP_29") (pintype "passive"))
      (node (ref "U3") (pin "3") (pinfunction "GND_3") (pintype "passive"))
      (node (ref "U4") (pin "9") (pinfunction "GND_9") (pintype "passive"))
      (node (ref "U5") (pin "8") (pinfunction "GND_8") (pintype "passive"))
      (node (ref "USB1") (pin "0") (pinfunction "MTN_0") (pintype "passive"))
      (node (ref "USB1") (pin "5") (pinfunction "V-_5") (pintype "passive"))
    )
    (net (code "34") (name "Net-(C10-Pad2)") (class "Default")
      (node (ref "C10") (pin "2") (pinfunction "2_2") (pintype "passive"))
      (node (ref "R4") (pin "1") (pinfunction "1_1") (pintype "passive"))
    )
    (net (code "35") (name "Net-(D1-K)") (class "Default")
      (node (ref "C3") (pin "1") (pinfunction "1_1") (pintype "passive"))
      (node (ref "D1") (pin "1") (pinfunction "K_1") (pintype "passive"))
      (node (ref "L1") (pin "1") (pinfunction "1_1") (pintype "passive"))
      (node (ref "U1") (pin "8") (pinfunction "PH_8") (pintype "passive"))
    )
    (net (code "36") (name "Net-(D2-VBUS)") (class "Default")
      (node (ref "C14") (pin "1") (pinfunction "1_1") (pintype "passive"))
      (node (ref "D2") (pin "5") (pinfunction "VBUS_5") (pintype "passive"))
      (node (ref "R14") (pin "2") (pinfunction "2_2") (pintype "passive"))
    )
    (net (code "37") (name "Net-(K1-Pad4)") (class "Default")
      (node (ref "K1") (pin "4") (pinfunction "4_4") (pintype "passive"))
      (node (ref "K2") (pin "3") (pinfunction "3_3") (pintype "passive"))
      (node (ref "RV1") (pin "1") (pinfunction "1_1") (pintype "passive"))
      (node (ref "RV2") (pin "2") (pinfunction "2_2") (pintype "passive"))
    )
    (net (code "38") (name "Net-(K2-Pad4)") (class "Default")
      (node (ref "K2") (pin "4") (pinfunction "4_4") (pintype "passive"))
      (node (ref "K3") (pin "3") (pinfunction "3_3") (pintype "passive"))
      (node (ref "RV2") (pin "1") (pinfunction "1_1") (pintype "passive"))
      (node (ref "RV3") (pin "2") (pinfunction "2_2") (pintype "passive"))
    )
    (net (code "39") (name "Net-(K3-Pad4)") (class "Default")
      (node (ref "K3") (pin "4") (pinfunction "4_4") (pintype "passive"))
      (node (ref "K4") (pin "3") (pinfunction "3_3") (pintype "passive"))
      (node (ref "RV3") (pin "1") (pinfunction "1_1") (pintype "passive"))
      (node (ref "RV4") (pin "2") (pinfunction "2_2") (pintype "passive"))
    )
    (net (code "40") (name "Net-(K4-Pad4)") (class "Default")
      (node (ref "K4") (pin "4") (pinfunction "4_4") (pintype "passive"))
      (node (ref "K5") (pin "4") (pinfunction "4_4") (pintype "passive"))
      (node (ref "RV4") (pin "1") (pinfunction "1_1") (pintype "passive"))
      (node (ref "RV5") (pin "1") (pinfunction "1_1") (pintype "passive"))
    )
    (net (code "41") (name "Net-(K5-Pad3)") (class "Default")
      (node (ref "K5") (pin "3") (pinfunction "3_3") (pintype "passive"))
      (node (ref "K6") (pin "4") (pinfunction "4_4") (pintype "passive"))
      (node (ref "RV5") (pin "2") (pinfunction "2_2") (pintype "passive"))
      (node (ref "RV6") (pin "1") (pinfunction "1_1") (pintype "passive"))
    )
    (net (code "42") (name "Net-(K6-Pad3)") (class "Default")
      (node (ref "K6") (pin "3") (pinfunction "3_3") (pintype "passive"))
      (node (ref "K7") (pin "4") (pinfunction "4_4") (pintype "passive"))
      (node (ref "RV6") (pin "2") (pinfunction "2_2") (pintype "passive"))
      (node (ref "RV7") (pin "1") (pinfunction "1_1") (pintype "passive"))
    )
    (net (code "43") (name "Net-(K7-Pad3)") (class "Default")
      (node (ref "K7") (pin "3") (pinfunction "3_3") (pintype "passive"))
      (node (ref "K8") (pin "4") (pinfunction "4_4") (pintype "passive"))
      (node (ref "RV7") (pin "2") (pinfunction "2_2") (pintype "passive"))
      (node (ref "RV8") (pin "1") (pinfunction "1_1") (pintype "passive"))
    )
    (net (code "44") (name "Net-(LED1-A)") (class "Default")
      (node (ref "LED1") (pin "2") (pinfunction "A_2") (pintype "passive"))
      (node (ref "R7") (pin "1") (pinfunction "1_1") (pintype "passive"))
    )
    (net (code "45") (name "Net-(LED2-A)") (class "Default")
      (node (ref "LED2") (pin "2") (pinfunction "A_2") (pintype "passive"))
      (node (ref "R10") (pin "1") (pinfunction "1_1") (pintype "passive"))
    )
    (net (code "46") (name "Net-(LED3-A)") (class "Default")
      (node (ref "LED3") (pin "2") (pinfunction "A_2") (pintype "passive"))
      (node (ref "R11") (pin "1") (pinfunction "1_1") (pintype "passive"))
    )
    (net (code "47") (name "Net-(Q1-B)") (class "Default")
      (node (ref "Q1") (pin "1") (pinfunction "B_1") (pintype "passive"))
      (node (ref "R12") (pin "1") (pinfunction "1_1") (pintype "passive"))
    )
    (net (code "48") (name "Net-(Q2-B)") (class "Default")
      (node (ref "Q2") (pin "1") (pinfunction "B_1") (pintype "passive"))
      (node (ref "R16") (pin "1") (pinfunction "1_1") (pintype "passive"))
    )
    (net (code "49") (name "Net-(U1-BOOT)") (class "Default")
      (node (ref "C3") (pin "2") (pinfunction "2_2") (pintype "passive"))
      (node (ref "U1") (pin "1") (pinfunction "BOOT_1") (pintype "passive"))
    )
    (net (code "50") (name "Net-(U1-COMP)") (class "Default")
      (node (ref "C10") (pin "1") (pinfunction "1_1") (pintype "passive"))
      (node (ref "C11") (pin "1") (pinfunction "1_1") (pintype "passive"))
      (node (ref "U1") (pin "6") (pinfunction "COMP_6") (pintype "passive"))
    )
    (net (code "51") (name "Net-(U1-EN)") (class "Default")
      (node (ref "R1") (pin "2") (pinfunction "2_2") (pintype "passive"))
      (node (ref "R3") (pin "1") (pinfunction "1_1") (pintype "passive"))
      (node (ref "U1") (pin "3") (pinfunction "EN_3") (pintype "passive"))
    )
    (net (code "52") (name "Net-(U1-SS)") (class "Default")
      (node (ref "C9") (pin "1") (pinfunction "1_1") (pintype "passive"))
      (node (ref "U1") (pin "4") (pinfunction "SS_4") (pintype "passive"))
    )
    (net (code "53") (name "Net-(U1-VSENSE)") (class "Default")
      (node (ref "R2") (pin "2") (pinfunction "2_2") (pintype "passive"))
      (node (ref "R5") (pin "1") (pinfunction "1_1") (pintype "passive"))
      (node (ref "U1") (pin "5") (pinfunction "VSENSE_5") (pintype "passive"))
    )
    (net (code "54") (name "Net-(U3-RST#)") (class "Default")
      (node (ref "R18") (pin "2") (pinfunction "2_2") (pintype "passive"))
      (node (ref "U3") (pin "9") (pinfunction "RST#_9") (pintype "passive"))
    )
    (net (code "55") (name "Net-(U3-RXD)") (class "Default")
      (node (ref "R8") (pin "2") (pinfunction "2_2") (pintype "passive"))
      (node (ref "U3") (pin "25") (pinfunction "RXD_25") (pintype "passive"))
    )
    (net (code "56") (name "Net-(U3-SUSPEND#)") (class "Default")
      (node (ref "R19") (pin "2") (pinfunction "2_2") (pintype "passive"))
      (node (ref "U3") (pin "11") (pinfunction "SUSPEND#_11") (pintype "passive"))
    )
    (net (code "57") (name "Net-(U3-TXD)") (class "Default")
      (node (ref "R9") (pin "2") (pinfunction "2_2") (pintype "passive"))
      (node (ref "U3") (pin "26") (pinfunction "TXD_26") (pintype "passive"))
    )
    (net (code "58") (name "Net-(U4-1B)") (class "Default")
      (node (ref "U4") (pin "1") (pinfunction "1B_1") (pintype "passive"))
      (node (ref "U5") (pin "15") (pinfunction "Q0_15") (pintype "passive"))
    )
    (net (code "59") (name "Net-(U4-2B)") (class "Default")
      (node (ref "U4") (pin "2") (pinfunction "2B_2") (pintype "passive"))
      (node (ref "U5") (pin "1") (pinfunction "Q1_1") (pintype "passive"))
    )
    (net (code "60") (name "Net-(U4-3B)") (class "Default")
      (node (ref "U4") (pin "3") (pinfunction "3B_3") (pintype "passive"))
      (node (ref "U5") (pin "2") (pinfunction "Q2_2") (pintype "passive"))
    )
    (net (code "61") (name "Net-(U4-4B)") (class "Default")
      (node (ref "U4") (pin "4") (pinfunction "4B_4") (pintype "passive"))
      (node (ref "U5") (pin "3") (pinfunction "Q3_3") (pintype "passive"))
    )
    (net (code "62") (name "Net-(U4-5B)") (class "Default")
      (node (ref "U4") (pin "5") (pinfunction "5B_5") (pintype "passive"))
      (node (ref "U5") (pin "4") (pinfunction "Q4_4") (pintype "passive"))
    )
    (net (code "63") (name "Net-(U4-6B)") (class "Default")
      (node (ref "U4") (pin "6") (pinfunction "6B_6") (pintype "passive"))
      (node (ref "U5") (pin "5") (pinfunction "Q5_5") (pintype "passive"))
    )
    (net (code "64") (name "Net-(U4-7B)") (class "Default")
      (node (ref "U4") (pin "7") (pinfunction "7B_7") (pintype "passive"))
      (node (ref "U5") (pin "6") (pinfunction "Q6_6") (pintype "passive"))
    )
    (net (code "65") (name "Net-(U4-8B)") (class "Default")
      (node (ref "U4") (pin "8") (pinfunction "8B_8") (pintype "passive"))
      (node (ref "U5") (pin "7") (pinfunction "Q7_7") (pintype "passive"))
    )
    (net (code "66") (name "Net-(USB1-D+)") (class "Default")
      (node (ref "D2") (pin "3") (pinfunction "IO2_3") (pintype "passive"))
      (node (ref "R17") (pin "1") (pinfunction "1_1") (pintype "passive"))
      (node (ref "USB1") (pin "3") (pinfunction "D+_3") (pintype "passive"))
    )
    (net (code "67") (name "Net-(USB1-D-)") (class "Default")
      (node (ref "D2") (pin "1") (pinfunction "IO1_1") (pintype "passive"))
      (node (ref "R15") (pin "1") (pinfunction "1_1") (pintype "passive"))
      (node (ref "USB1") (pin "2") (pinfunction "D-_2") (pintype "passive"))
    )
    (net (code "68") (name "Net-(USB1-V+)") (class "Default")
      (node (ref "R13") (pin "2") (pinfunction "2_2") (pintype "passive"))
      (node (ref "USB1") (pin "1") (pinfunction "V+_1") (pintype "passive"))
    )
    (net (code "69") (name "unconnected-(P3-Pad4)") (class "Default")
      (node (ref "P3") (pin "4") (pinfunction "4_4") (pintype "passive"))
    )
    (net (code "70") (name "unconnected-(P3-Pad5)") (class "Default")
      (node (ref "P3") (pin "5") (pinfunction "5_5") (pintype "passive"))
    )
    (net (code "71") (name "unconnected-(P6-Pad2)") (class "Default")
      (node (ref "P6") (pin "2") (pinfunction "2_2") (pintype "passive"))
    )
    (net (code "72") (name "unconnected-(P6-Pad3)") (class "Default")
      (node (ref "P6") (pin "3") (pinfunction "3_3") (pintype "passive"))
    )
    (net (code "73") (name "unconnected-(P6-Pad4)") (class "Default")
      (node (ref "P6") (pin "4") (pinfunction "4_4") (pintype "passive"))
    )
    (net (code "74") (name "unconnected-(P6-Pad5)") (class "Default")
      (node (ref "P6") (pin "5") (pinfunction "5_5") (pintype "passive"))
    )
    (net (code "75") (name "unconnected-(P6-Pad6)") (class "Default")
      (node (ref "P6") (pin "6") (pinfunction "6_6") (pintype "passive"))
    )
    (net (code "76") (name "unconnected-(U2-CLK-Pad19)") (class "Default")
      (node (ref "U2") (pin "19") (pinfunction "CLK_19") (pintype "passive"))
    )
    (net (code "77") (name "unconnected-(U2-CMD-Pad18)") (class "Default")
      (node (ref "U2") (pin "18") (pinfunction "CMD_18") (pintype "passive"))
    )
    (net (code "78") (name "unconnected-(U2-IO12-Pad13)") (class "Default")
      (node (ref "U2") (pin "13") (pinfunction "IO12_13") (pintype "passive"))
    )
    (net (code "79") (name "unconnected-(U2-IO13-Pad15)") (class "Default")
      (node (ref "U2") (pin "15") (pinfunction "IO13_15") (pintype "passive"))
    )
    (net (code "80") (name "unconnected-(U2-IO14-Pad12)") (class "Default")
      (node (ref "U2") (pin "12") (pinfunction "IO14_12") (pintype "passive"))
    )
    (net (code "81") (name "unconnected-(U2-IO15-Pad22)") (class "Default")
      (node (ref "U2") (pin "22") (pinfunction "IO15_22") (pintype "passive"))
    )
    (net (code "82") (name "unconnected-(U2-IO16-Pad26)") (class "Default")
      (node (ref "U2") (pin "26") (pinfunction "IO16_26") (pintype "passive"))
    )
    (net (code "83") (name "unconnected-(U2-IO21-Pad32)") (class "Default")
      (node (ref "U2") (pin "32") (pinfunction "IO21_32") (pintype "passive"))
    )
    (net (code "84") (name "unconnected-(U2-IO22-Pad35)") (class "Default")
      (node (ref "U2") (pin "35") (pinfunction "IO22_35") (pintype "passive"))
    )
    (net (code "85") (name "unconnected-(U2-IO23-Pad36)") (class "Default")
      (node (ref "U2") (pin "36") (pinfunction "IO23_36") (pintype "passive"))
    )
    (net (code "86") (name "unconnected-(U2-IO25-Pad9)") (class "Default")
      (node (ref "U2") (pin "9") (pinfunction "IO25_9") (pintype "passive"))
    )
    (net (code "87") (name "unconnected-(U2-IO26-Pad10)") (class "Default")
      (node (ref "U2") (pin "10") (pinfunction "IO26_10") (pintype "passive"))
    )
    (net (code "88") (name "unconnected-(U2-IO27-Pad11)") (class "Default")
      (node (ref "U2") (pin "11") (pinfunction "IO27_11") (pintype "passive"))
    )
    (net (code "89") (name "unconnected-(U2-IO32-Pad7)") (class "Default")
      (node (ref "U2") (pin "7") (pinfunction "IO32_7") (pintype "passive"))
    )
    (net (code "90") (name "unconnected-(U2-IO33-Pad8)") (class "Default")
      (node (ref "U2") (pin "8") (pinfunction "IO33_8") (pintype "passive"))
    )
    (net (code "91") (name "unconnected-(U2-IO34-Pad5)") (class "Default")
      (node (ref "U2") (pin "5") (pinfunction "IO34_5") (pintype "passive"))
    )
    (net (code "92") (name "unconnected-(U2-IO35-Pad6)") (class "Default")
      (node (ref "U2") (pin "6") (pinfunction "IO35_6") (pintype "passive"))
    )
    (net (code "93") (name "unconnected-(U2-NC-Pad31)") (class "Default")
      (node (ref "U2") (pin "31") (pinfunction "NC_31") (pintype "passive"))
    )
    (net (code "94") (name "unconnected-(U2-SD0-Pad20)") (class "Default")
      (node (ref "U2") (pin "20") (pinfunction "SD0_20") (pintype "passive"))
    )
    (net (code "95") (name "unconnected-(U2-SD1-Pad21)") (class "Default")
      (node (ref "U2") (pin "21") (pinfunction "SD1_21") (pintype "passive"))
    )
    (net (code "96") (name "unconnected-(U2-SD2-Pad16)") (class "Default")
      (node (ref "U2") (pin "16") (pinfunction "SD2_16") (pintype "passive"))
    )
    (net (code "97") (name "unconnected-(U2-SD3-Pad17)") (class "Default")
      (node (ref "U2") (pin "17") (pinfunction "SD3_17") (pintype "passive"))
    )
    (net (code "98") (name "unconnected-(U2-SENSOR_VN-Pad4)") (class "Default")
      (node (ref "U2") (pin "4") (pinfunction "SENSOR_VN_4") (pintype "passive"))
    )
    (net (code "99") (name "unconnected-(U2-SENSOR_VP-Pad3)") (class "Default")
      (node (ref "U2") (pin "3") (pinfunction "SENSOR_VP_3") (pintype "passive"))
    )
    (net (code "100") (name "unconnected-(U3-CTS-Pad23)") (class "Default")
      (node (ref "U3") (pin "23") (pinfunction "CTS_23") (pintype "passive"))
    )
    (net (code "101") (name "unconnected-(U3-DCD-Pad1)") (class "Default")
      (node (ref "U3") (pin "1") (pinfunction "DCD_1") (pintype "passive"))
    )
    (net (code "102") (name "unconnected-(U3-DSR-Pad27)") (class "Default")
      (node (ref "U3") (pin "27") (pinfunction "DSR_27") (pintype "passive"))
    )
    (net (code "103") (name "unconnected-(U3-NC-Pad10)") (class "Default")
      (node (ref "U3") (pin "10") (pinfunction "NC_10") (pintype "passive"))
    )
    (net (code "104") (name "unconnected-(U3-NC-Pad13)") (class "Default")
      (node (ref "U3") (pin "13") (pinfunction "NC_13") (pintype "passive"))
    )
    (net (code "105") (name "unconnected-(U3-NC-Pad14)") (class "Default")
      (node (ref "U3") (pin "14") (pinfunction "NC_14") (pintype "passive"))
    )
    (net (code "106") (name "unconnected-(U3-NC-Pad15)") (class "Default")
      (node (ref "U3") (pin "15") (pinfunction "NC_15") (pintype "passive"))
    )
    (net (code "107") (name "unconnected-(U3-NC-Pad16)") (class "Default")
      (node (ref "U3") (pin "16") (pinfunction "NC_16") (pintype "passive"))
    )
    (net (code "108") (name "unconnected-(U3-NC-Pad17)") (class "Default")
      (node (ref "U3") (pin "17") (pinfunction "NC_17") (pintype "passive"))
    )
    (net (code "109") (name "unconnected-(U3-NC-Pad18)") (class "Default")
      (node (ref "U3") (pin "18") (pinfunction "NC_18") (pintype "passive"))
    )
    (net (code "110") (name "unconnected-(U3-NC-Pad19)") (class "Default")
      (node (ref "U3") (pin "19") (pinfunction "NC_19") (pintype "passive"))
    )
    (net (code "111") (name "unconnected-(U3-NC-Pad20)") (class "Default")
      (node (ref "U3") (pin "20") (pinfunction "NC_20") (pintype "passive"))
    )
    (net (code "112") (name "unconnected-(U3-NC-Pad21)") (class "Default")
      (node (ref "U3") (pin "21") (pinfunction "NC_21") (pintype "passive"))
    )
    (net (code "113") (name "unconnected-(U3-NC-Pad22)") (class "Default")
      (node (ref "U3") (pin "22") (pinfunction "NC_22") (pintype "passive"))
    )
    (net (code "114") (name "unconnected-(U3-RI-Pad2)") (class "Default")
      (node (ref "U3") (pin "2") (pinfunction "RI_2") (pintype "passive"))
    )
    (net (code "115") (name "unconnected-(U3-SUSPEND-Pad12)") (class "Default")
      (node (ref "U3") (pin "12") (pinfunction "SUSPEND_12") (pintype "passive"))
    )
    (net (code "116") (name "unconnected-(USB1-ID-Pad4)") (class "Default")
      (node (ref "USB1") (pin "4") (pinfunction "ID_4") (pintype "passive"))
    )
  )
)
